# OutletC.net
KiCad netlist of a schematic drawn in EAGLE
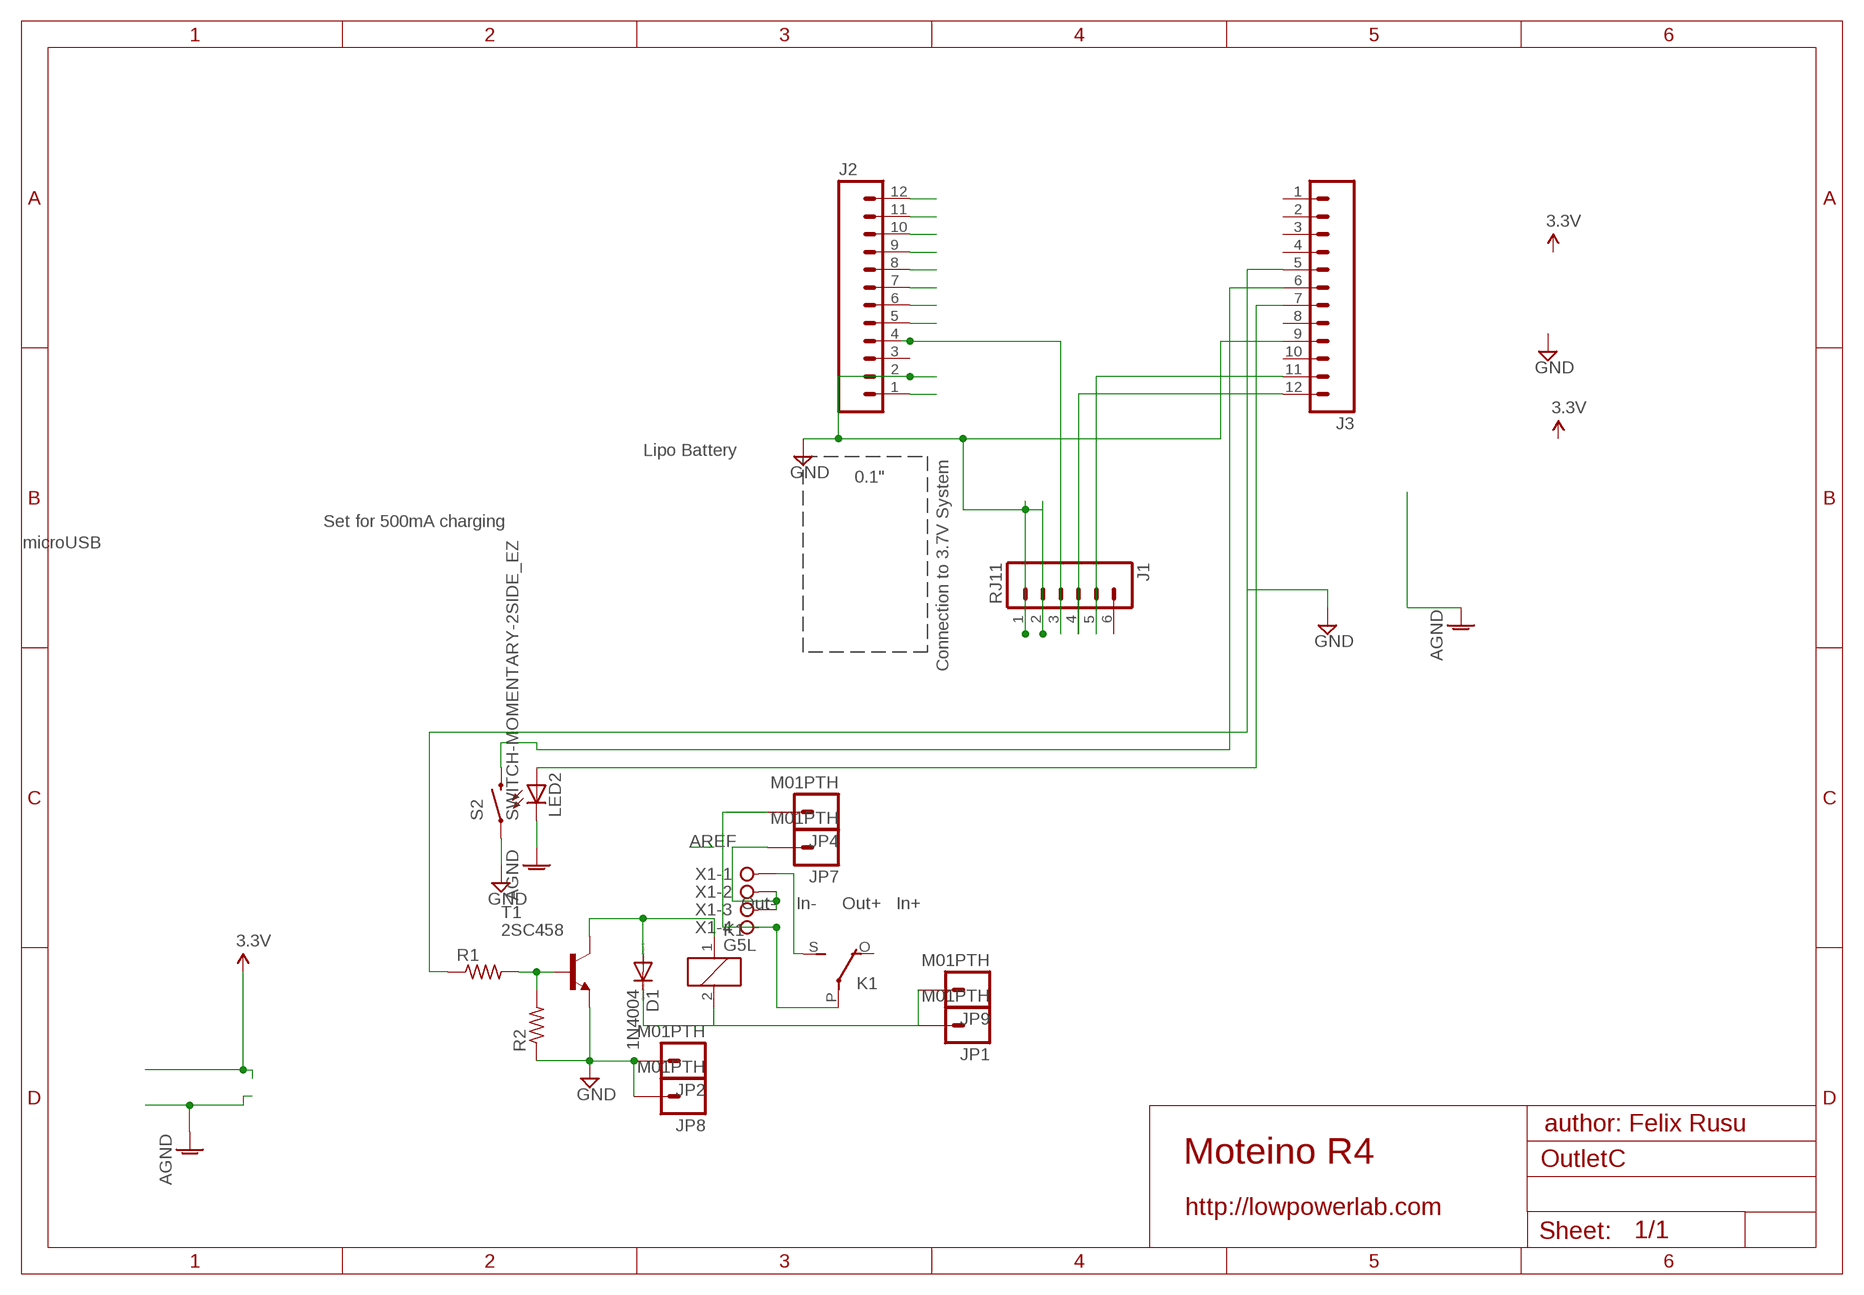
[diagram p0: schematic, sheet 1]

(export (version "E")
  (design (tool "Eeschema 10.0.6"))
  (components
    (comp (ref "D1")
      (value "1N4004")
      (footprint "eagle-import:DO41-10")
      (libsource (lib "eagle-import") (part "1N4004"))
    )
    (comp (ref "J1")
      (value "RJ11")
      (footprint "eagle-import:RJ11-6")
      (libsource (lib "eagle-import") (part "RJ11-6PTH"))
    )
    (comp (ref "J2")
      (value "M12PTH")
      (footprint "eagle-import:1X12")
      (libsource (lib "eagle-import") (part "M12PTH"))
    )
    (comp (ref "J3")
      (value "M12PTH")
      (footprint "eagle-import:1X12")
      (libsource (lib "eagle-import") (part "M12PTH"))
    )
    (comp (ref "JP1")
      (value "M01PTH")
      (footprint "eagle-import:1X01")
      (libsource (lib "eagle-import") (part "M01PTH"))
    )
    (comp (ref "JP2")
      (value "M01PTH")
      (footprint "eagle-import:1X01")
      (libsource (lib "eagle-import") (part "M01PTH"))
    )
    (comp (ref "JP4")
      (value "M01PTH")
      (footprint "eagle-import:1X01")
      (libsource (lib "eagle-import") (part "M01PTH"))
    )
    (comp (ref "JP7")
      (value "M01PTH")
      (footprint "eagle-import:1X01")
      (libsource (lib "eagle-import") (part "M01PTH"))
    )
    (comp (ref "JP8")
      (value "M01PTH")
      (footprint "eagle-import:1X01")
      (libsource (lib "eagle-import") (part "M01PTH"))
    )
    (comp (ref "JP9")
      (value "M01PTH")
      (footprint "eagle-import:1X01")
      (libsource (lib "eagle-import") (part "M01PTH"))
    )
    (comp (ref "K1")
      (value "G5L")
      (footprint "eagle-import:G5LE")
      (libsource (lib "eagle-import") (part "G5L"))
    )
    (comp (ref "LED2")
      (value "LED3MM")
      (footprint "eagle-import:LED3MM")
      (libsource (lib "eagle-import") (part "LED3MM"))
    )
    (comp (ref "R1")
      (value "R-US_0204/7")
      (footprint "eagle-import:0204_7")
      (libsource (lib "eagle-import") (part "R-US_0204/7"))
    )
    (comp (ref "R2")
      (value "R-US_0204/7")
      (footprint "eagle-import:0204_7")
      (libsource (lib "eagle-import") (part "R-US_0204/7"))
    )
    (comp (ref "S2")
      (value "SWITCH-MOMENTARY-2SIDE_EZ")
      (footprint "eagle-import:TACTILE-PTH-SIDEEZ")
      (libsource (lib "eagle-import") (part "SWITCH-MOMENTARY-2SIDE_EZ"))
    )
    (comp (ref "T1")
      (value "2SC458")
      (footprint "eagle-import:TO92-ECB")
      (libsource (lib "eagle-import") (part "2SC458"))
    )
    (comp (ref "X1")
      (value "Out- In- Out+ In+")
      (footprint "eagle-import:W237-4P")
      (fields (field (name "MF") "In-") (field (name "MPN") "Out-"))
      (libsource (lib "eagle-import") (part "W237-04P"))
    )
  )
  (nets
    (net (code "3") (name "AGND") (class "Default")
      (node (ref "LED2") (pin "K") (pinfunction "C_K") (pintype "passive"))
    )
    (net (code "4") (name "GND") (class "Default")
      (node (ref "J1") (pin "1") (pinfunction "1_1") (pintype "passive"))
      (node (ref "J1") (pin "2") (pinfunction "2_2") (pintype "passive"))
      (node (ref "J2") (pin "2") (pinfunction "2_2") (pintype "passive"))
      (node (ref "J3") (pin "9") (pinfunction "9_9") (pintype "passive"))
      (node (ref "JP2") (pin "1") (pinfunction "1_1") (pintype "passive"))
      (node (ref "JP8") (pin "1") (pinfunction "1_1") (pintype "passive"))
      (node (ref "R2") (pin "1") (pinfunction "1_1") (pintype "passive"))
      (node (ref "S2") (pin "1") (pinfunction "1_1") (pintype "passive"))
      (node (ref "T1") (pin "E") (pinfunction "E_E") (pintype "passive"))
    )
    (net (code "5") (name "Net-(D1-PadA)") (class "Default")
      (node (ref "D1") (pin "A") (pinfunction "A_A") (pintype "passive"))
      (node (ref "K1") (pin "1") (pinfunction "1_1") (pintype "passive"))
      (node (ref "T1") (pin "C") (pinfunction "C_C") (pintype "passive"))
    )
    (net (code "6") (name "Net-(D1-PadC)") (class "Default")
      (node (ref "D1") (pin "C") (pinfunction "C_C") (pintype "passive"))
      (node (ref "JP1") (pin "1") (pinfunction "1_1") (pintype "passive"))
      (node (ref "JP9") (pin "1") (pinfunction "1_1") (pintype "passive"))
      (node (ref "K1") (pin "2") (pinfunction "2_2") (pintype "passive"))
    )
    (net (code "7") (name "Net-(J1-Pad3)") (class "Default")
      (node (ref "J1") (pin "3") (pinfunction "3_3") (pintype "passive"))
      (node (ref "J2") (pin "4") (pinfunction "4_4") (pintype "passive"))
    )
    (net (code "8") (name "Net-(J1-Pad4)") (class "Default")
      (node (ref "J1") (pin "4") (pinfunction "4_4") (pintype "passive"))
      (node (ref "J3") (pin "12") (pinfunction "12_12") (pintype "passive"))
    )
    (net (code "9") (name "Net-(J1-Pad5)") (class "Default")
      (node (ref "J1") (pin "5") (pinfunction "5_5") (pintype "passive"))
      (node (ref "J3") (pin "11") (pinfunction "11_11") (pintype "passive"))
    )
    (net (code "10") (name "Net-(J3-Pad5)") (class "Default")
      (node (ref "J3") (pin "5") (pinfunction "5_5") (pintype "passive"))
      (node (ref "R1") (pin "1") (pinfunction "1_1") (pintype "passive"))
    )
    (net (code "11") (name "Net-(J3-Pad6)") (class "Default")
      (node (ref "J3") (pin "6") (pinfunction "6_6") (pintype "passive"))
      (node (ref "S2") (pin "2") (pinfunction "2_2") (pintype "passive"))
    )
    (net (code "12") (name "Net-(J3-Pad7)") (class "Default")
      (node (ref "J3") (pin "7") (pinfunction "7_7") (pintype "passive"))
      (node (ref "LED2") (pin "A") (pinfunction "A_A") (pintype "passive"))
    )
    (net (code "13") (name "Net-(R1-Pad2)") (class "Default")
      (node (ref "R1") (pin "2") (pinfunction "2_2") (pintype "passive"))
      (node (ref "R2") (pin "2") (pinfunction "2_2") (pintype "passive"))
      (node (ref "T1") (pin "B") (pinfunction "B_B") (pintype "passive"))
    )
    (net (code "14") (name "Net-(X1A-KL)") (class "Default")
      (node (ref "K1") (pin "S") (pinfunction "S_S") (pintype "passive"))
      (node (ref "X1") (pin "1") (pinfunction "KL_1") (pintype "passive"))
    )
    (net (code "15") (name "Net-(X1B-KL)") (class "Default")
      (node (ref "JP7") (pin "1") (pinfunction "1_1") (pintype "passive"))
      (node (ref "X1") (pin "2") (pinfunction "KL_2") (pintype "passive"))
      (node (ref "X1") (pin "3") (pinfunction "KL_3") (pintype "passive"))
    )
    (net (code "16") (name "Net-(X1D-KL)") (class "Default")
      (node (ref "JP4") (pin "1") (pinfunction "1_1") (pintype "passive"))
      (node (ref "K1") (pin "P") (pinfunction "P_P") (pintype "passive"))
      (node (ref "X1") (pin "4") (pinfunction "KL_4") (pintype "passive"))
    )
    (net (code "17") (name "unconnected-(J1-Pad6)") (class "Default")
      (node (ref "J1") (pin "6") (pinfunction "6_6") (pintype "passive"))
    )
    (net (code "18") (name "unconnected-(J2-Pad1)") (class "Default")
      (node (ref "J2") (pin "1") (pinfunction "1_1") (pintype "passive"))
    )
    (net (code "19") (name "unconnected-(J2-Pad3)") (class "Default")
      (node (ref "J2") (pin "3") (pinfunction "3_3") (pintype "passive"))
    )
    (net (code "20") (name "unconnected-(J2-Pad5)") (class "Default")
      (node (ref "J2") (pin "5") (pinfunction "5_5") (pintype "passive"))
    )
    (net (code "21") (name "unconnected-(J2-Pad6)") (class "Default")
      (node (ref "J2") (pin "6") (pinfunction "6_6") (pintype "passive"))
    )
    (net (code "22") (name "unconnected-(J2-Pad7)") (class "Default")
      (node (ref "J2") (pin "7") (pinfunction "7_7") (pintype "passive"))
    )
    (net (code "23") (name "unconnected-(J2-Pad8)") (class "Default")
      (node (ref "J2") (pin "8") (pinfunction "8_8") (pintype "passive"))
    )
    (net (code "24") (name "unconnected-(J2-Pad9)") (class "Default")
      (node (ref "J2") (pin "9") (pinfunction "9_9") (pintype "passive"))
    )
    (net (code "25") (name "unconnected-(J2-Pad10)") (class "Default")
      (node (ref "J2") (pin "10") (pinfunction "10_10") (pintype "passive"))
    )
    (net (code "26") (name "unconnected-(J2-Pad11)") (class "Default")
      (node (ref "J2") (pin "11") (pinfunction "11_11") (pintype "passive"))
    )
    (net (code "27") (name "unconnected-(J2-Pad12)") (class "Default")
      (node (ref "J2") (pin "12") (pinfunction "12_12") (pintype "passive"))
    )
    (net (code "28") (name "unconnected-(J3-Pad1)") (class "Default")
      (node (ref "J3") (pin "1") (pinfunction "1_1") (pintype "passive"))
    )
    (net (code "29") (name "unconnected-(J3-Pad2)") (class "Default")
      (node (ref "J3") (pin "2") (pinfunction "2_2") (pintype "passive"))
    )
    (net (code "30") (name "unconnected-(J3-Pad3)") (class "Default")
      (node (ref "J3") (pin "3") (pinfunction "3_3") (pintype "passive"))
    )
    (net (code "31") (name "unconnected-(J3-Pad4)") (class "Default")
      (node (ref "J3") (pin "4") (pinfunction "4_4") (pintype "passive"))
    )
    (net (code "32") (name "unconnected-(J3-Pad8)") (class "Default")
      (node (ref "J3") (pin "8") (pinfunction "8_8") (pintype "passive"))
    )
    (net (code "33") (name "unconnected-(J3-Pad10)") (class "Default")
      (node (ref "J3") (pin "10") (pinfunction "10_10") (pintype "passive"))
    )
    (net (code "34") (name "unconnected-(K1-PadO)") (class "Default")
      (node (ref "K1") (pin "O") (pinfunction "O_O") (pintype "passive"))
    )
  )
)
